# Power_Monitor.net
KiCad netlist of a schematic drawn in Altium Designer
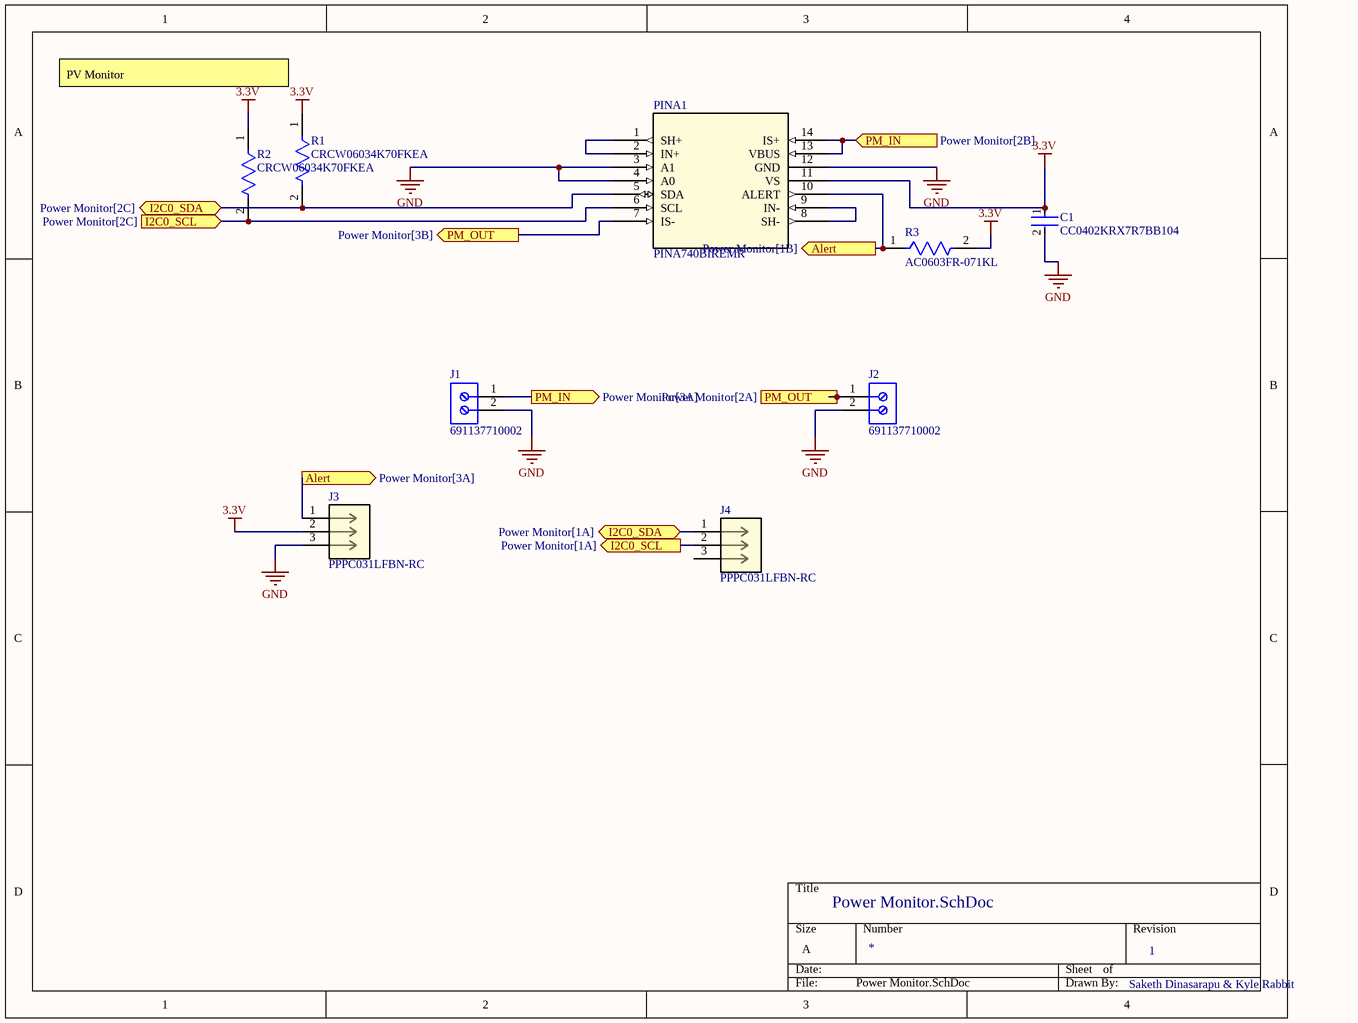
[diagram p0: Power Monitor.SchDoc]

(export (version "E")
  (design (tool "Eeschema 10.0.6"))
  (components
    (comp (ref "C1")
      (value "CC0402KRX7R7BB104")
      (footprint "FP-CC0402-MFG")
      (description "CAP CER 0.1UF 16V X7R 0402")
      (fields (field (name "MANUFACTURER") "YAGEO") (field (name "TOLERANCE") "0.1"))
      (libsource (lib "Altium Content Vault") (part "11868f565c42a9108669ba33697ecf6"))
    )
    (comp (ref "J1")
      (value "691137710002")
      (footprint "691137710002")
      (libsource (lib "Altium Content Vault") (part "TBL - 1R - 02P - Screw"))
    )
    (comp (ref "J2")
      (value "691137710002")
      (footprint "691137710002")
      (libsource (lib "Altium Content Vault") (part "TBL - 1R - 02P - Screw"))
    )
    (comp (ref "J3")
      (value "PPPC031LFBN-RC")
      (footprint "CONN_PPPC031LFBN-RC_SUL")
      (description "No Description Available")
      (libsource (lib "PPPC031LFBN-RC") (part "PPPC031LFBN-RC"))
    )
    (comp (ref "J4")
      (value "PPPC031LFBN-RC")
      (footprint "CONN_PPPC031LFBN-RC_SUL")
      (description "No Description Available")
      (libsource (lib "PPPC031LFBN-RC") (part "PPPC031LFBN-RC"))
    )
    (comp (ref "PINA1")
      (value "PINA740BIREMR")
      (footprint "VQFN14_REM_TEX")
      (description "No Description Available")
      (libsource (lib "PINA740BIREMR") (part "PINA740BIREMR"))
    )
    (comp (ref "R1")
      (value "CRCW06034K70FKEA")
      (footprint "FP-CRCW0603-e3-IPC_A")
      (description "RES Thick Film, 4.7kΩ, 1%, 0.1W, 100ppm/°C, 0603")
      (fields (field (name "TOLERANCE") "1%"))
      (libsource (lib "Altium Content Vault") (part "1029c3af85768c4190bb7ad29bc67b5"))
    )
    (comp (ref "R2")
      (value "CRCW06034K70FKEA")
      (footprint "FP-CRCW0603-e3-IPC_A")
      (description "RES Thick Film, 4.7kΩ, 1%, 0.1W, 100ppm/°C, 0603")
      (fields (field (name "TOLERANCE") "1%"))
      (libsource (lib "Altium Content Vault") (part "1029c3af85768c4190bb7ad29bc67b5"))
    )
    (comp (ref "R3")
      (value "AC0603FR-071KL")
      (footprint "FP-AC0603-IPC_B")
      (description "RES 1kΩ 1.00% 0.1W 0603")
      (fields (field (name "TOLERANCE") "1%"))
      (libsource (lib "Altium Content Vault") (part "1029c3af85768c4190bb7ad29bc67b5"))
    )
  )
  (nets
    (net (code "1") (name "/Alert") (class "Default")
      (node (ref "J3") (pin "1") (pinfunction "1_1") (pintype "passive"))
      (node (ref "PINA1") (pin "10") (pinfunction "ALERT_10") (pintype "output"))
      (node (ref "R3") (pin "1") (pinfunction "1_1") (pintype "passive"))
    )
    (net (code "2") (name "/I2C0_SCL") (class "Default")
      (node (ref "J4") (pin "2") (pinfunction "2_2") (pintype "passive"))
      (node (ref "PINA1") (pin "6") (pinfunction "SCL_6") (pintype "input"))
      (node (ref "R2") (pin "2") (pinfunction "2_2") (pintype "passive"))
    )
    (net (code "3") (name "/I2C0_SDA") (class "Default")
      (node (ref "J4") (pin "1") (pinfunction "1_1") (pintype "passive"))
      (node (ref "PINA1") (pin "5") (pinfunction "SDA_5") (pintype "bidirectional"))
      (node (ref "R1") (pin "2") (pinfunction "2_2") (pintype "passive"))
    )
    (net (code "4") (name "/PM_IN") (class "Default")
      (node (ref "J1") (pin "1") (pinfunction "1_1") (pintype "passive"))
      (node (ref "PINA1") (pin "13") (pinfunction "VBUS_13") (pintype "input"))
      (node (ref "PINA1") (pin "14") (pinfunction "IS+_14") (pintype "input"))
    )
    (net (code "5") (name "/PM_OUT") (class "Default")
      (node (ref "J2") (pin "1") (pinfunction "1_1") (pintype "passive"))
      (node (ref "PINA1") (pin "7") (pinfunction "IS-_7") (pintype "input"))
    )
    (net (code "6") (name "3.3V") (class "Default")
      (node (ref "C1") (pin "1") (pinfunction "1_1") (pintype "passive"))
      (node (ref "J3") (pin "2") (pinfunction "2_2") (pintype "passive"))
      (node (ref "PINA1") (pin "11") (pinfunction "VS_11") (pintype "power_in"))
      (node (ref "R1") (pin "1") (pinfunction "1_1") (pintype "passive"))
      (node (ref "R2") (pin "1") (pinfunction "1_1") (pintype "passive"))
      (node (ref "R3") (pin "2") (pinfunction "2_2") (pintype "passive"))
    )
    (net (code "7") (name "GND") (class "Default")
      (node (ref "C1") (pin "2") (pinfunction "2_2") (pintype "passive"))
      (node (ref "J1") (pin "2") (pinfunction "2_2") (pintype "passive"))
      (node (ref "J2") (pin "2") (pinfunction "2_2") (pintype "passive"))
      (node (ref "J3") (pin "3") (pinfunction "3_3") (pintype "passive"))
      (node (ref "PINA1") (pin "12") (pinfunction "GND_12") (pintype "power_in"))
      (node (ref "PINA1") (pin "3") (pinfunction "A1_3") (pintype "input"))
      (node (ref "PINA1") (pin "4") (pinfunction "A0_4") (pintype "input"))
    )
    (net (code "8") (name "Net-(PINA1-IN+)") (class "Default")
      (node (ref "PINA1") (pin "1") (pinfunction "SH+_1") (pintype "output"))
      (node (ref "PINA1") (pin "2") (pinfunction "IN+_2") (pintype "input"))
    )
    (net (code "9") (name "Net-(PINA1-IN-)") (class "Default")
      (node (ref "PINA1") (pin "8") (pinfunction "SH-_8") (pintype "output"))
      (node (ref "PINA1") (pin "9") (pinfunction "IN-_9") (pintype "input"))
    )
    (net (code "10") (name "unconnected-(J4-Pad3)") (class "Default")
      (node (ref "J4") (pin "3") (pinfunction "3_3") (pintype "passive"))
    )
  )
)
